# AUDIO.net
KiCad netlist of a schematic drawn in Altium Designer
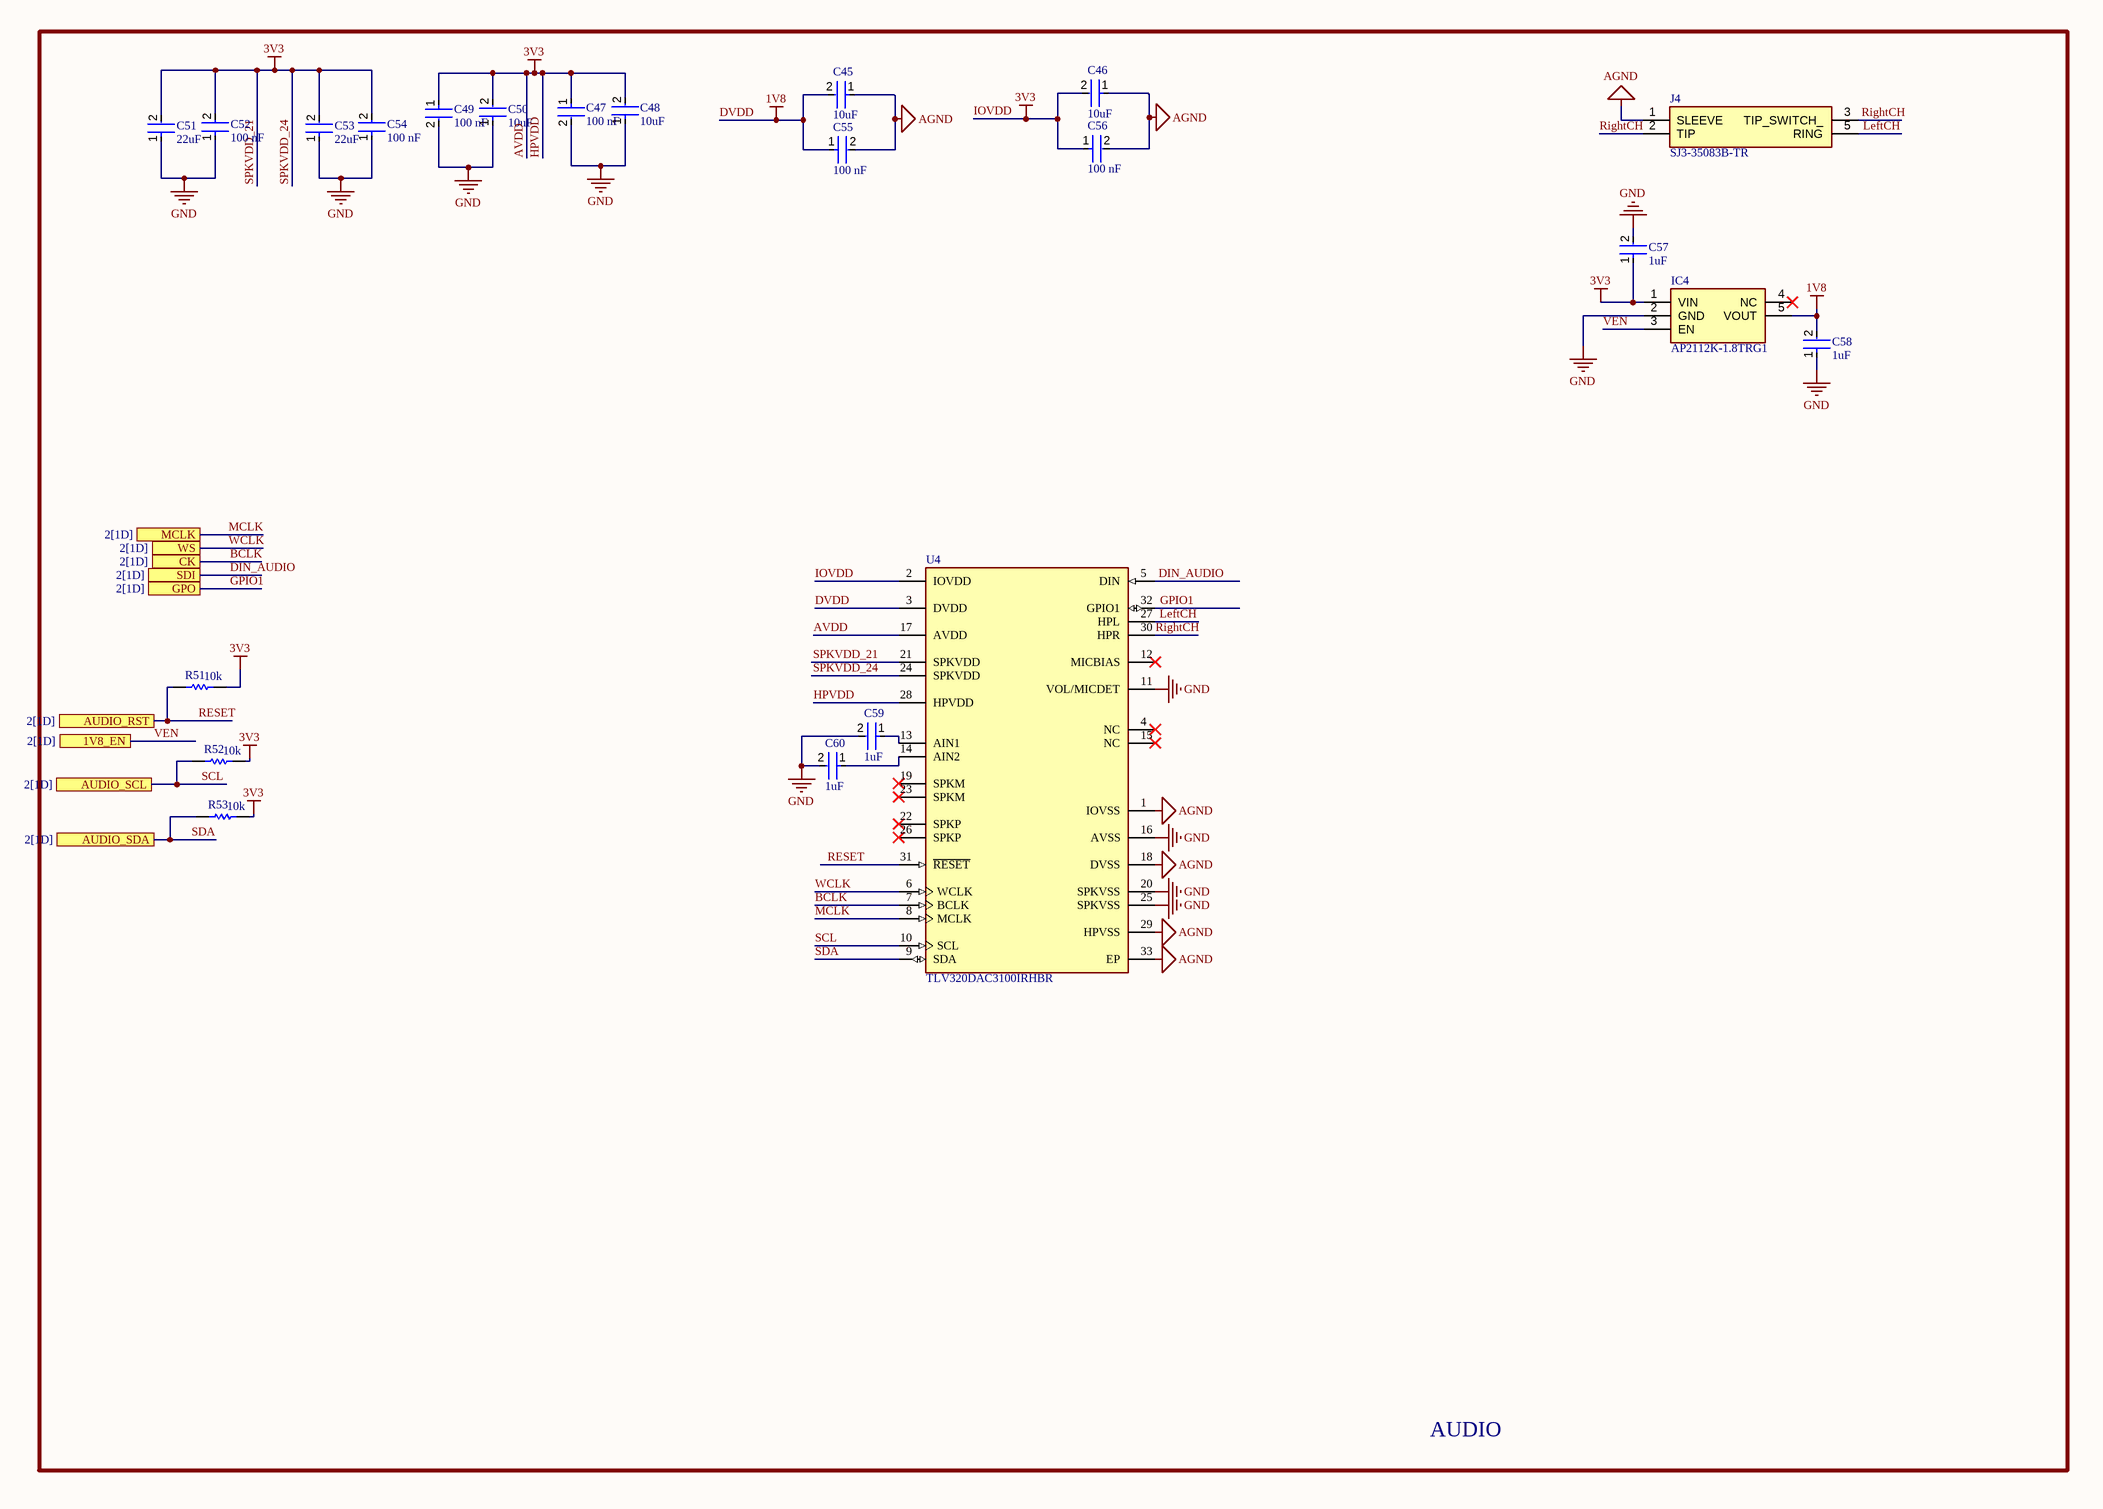
[diagram p0: AUDIO.SchDoc]

(export (version "E")
  (design (tool "Eeschema 10.0.6"))
  (components
    (comp (ref "C45")
      (value "GRM21BR61E106MA73L")
      (footprint "FP-GRM21B-0_15-IPC_A")
      (description "Chip Multilayer Ceramic Capacitors for General Purpose, 0805, 10uF, X5R, 15%, 20%, 25V")
      (fields (field (name "TOLERANCE") "20%") (field (name "CAPACITANCE") "10uF"))
      (libsource (lib "Altium Content Vault") (part "b4654b650e69147ec39a6b967a45e02"))
    )
    (comp (ref "C46")
      (value "GRM21BR61E106MA73L")
      (footprint "FP-GRM21B-0_15-IPC_A")
      (description "Chip Multilayer Ceramic Capacitors for General Purpose, 0805, 10uF, X5R, 15%, 20%, 25V")
      (fields (field (name "TOLERANCE") "20%") (field (name "CAPACITANCE") "10uF"))
      (libsource (lib "Altium Content Vault") (part "b4654b650e69147ec39a6b967a45e02"))
    )
    (comp (ref "C47")
      (value "100 nF")
      (footprint "FP-CC0603-DA-MFG")
      (description "CAP CER 0.1UF 16V X7R 0603")
      (fields
        (field (name "OCTOPART") "https://octopart.com/cc0603krx7r7bb104-yageo-192941")
        (field (name "TOLERANCE") "0.1")
      )
      (libsource (lib "Altium Content Vault") (part "11868f565c42a9108669ba33697ecf6"))
    )
    (comp (ref "C48")
      (value "GRM21BR61E106MA73L")
      (footprint "FP-GRM21B-0_15-IPC_A")
      (description "Chip Multilayer Ceramic Capacitors for General Purpose, 0805, 10uF, X5R, 15%, 20%, 25V")
      (fields (field (name "TOLERANCE") "20%") (field (name "CAPACITANCE") "10uF"))
      (libsource (lib "Altium Content Vault") (part "b4654b650e69147ec39a6b967a45e02"))
    )
    (comp (ref "C49")
      (value "100 nF")
      (footprint "FP-CC0603-DA-MFG")
      (description "CAP CER 0.1UF 16V X7R 0603")
      (fields
        (field (name "OCTOPART") "https://octopart.com/cc0603krx7r7bb104-yageo-192941")
        (field (name "TOLERANCE") "0.1")
      )
      (libsource (lib "Altium Content Vault") (part "11868f565c42a9108669ba33697ecf6"))
    )
    (comp (ref "C50")
      (value "GRM21BR61E106MA73L")
      (footprint "FP-GRM21B-0_15-IPC_A")
      (description "Chip Multilayer Ceramic Capacitors for General Purpose, 0805, 10uF, X5R, 15%, 20%, 25V")
      (fields (field (name "TOLERANCE") "20%") (field (name "CAPACITANCE") "10uF"))
      (libsource (lib "Altium Content Vault") (part "b4654b650e69147ec39a6b967a45e02"))
    )
    (comp (ref "C51")
      (value "EMK325B7226MM-PR")
      (footprint "FP-1210-L_3_2_0_3-W_2_5_0-IPC_A")
      (description "None")
      (fields (field (name "CAPACITANCE") "22uF") (field (name "TOLERANCE") "20%"))
      (libsource (lib "Altium Content Vault") (part "02cd4be3c70576c341d710602a673aa"))
    )
    (comp (ref "C52")
      (value "100 nF")
      (footprint "FP-CC0603-DA-MFG")
      (description "CAP CER 0.1UF 16V X7R 0603")
      (fields
        (field (name "OCTOPART") "https://octopart.com/cc0603krx7r7bb104-yageo-192941")
        (field (name "TOLERANCE") "0.1")
      )
      (libsource (lib "Altium Content Vault") (part "11868f565c42a9108669ba33697ecf6"))
    )
    (comp (ref "C53")
      (value "EMK325B7226MM-PR")
      (footprint "FP-1210-L_3_2_0_3-W_2_5_0-IPC_A")
      (description "None")
      (fields (field (name "CAPACITANCE") "22uF") (field (name "TOLERANCE") "20%"))
      (libsource (lib "Altium Content Vault") (part "02cd4be3c70576c341d710602a673aa"))
    )
    (comp (ref "C54")
      (value "100 nF")
      (footprint "FP-CC0603-DA-MFG")
      (description "CAP CER 0.1UF 16V X7R 0603")
      (fields
        (field (name "OCTOPART") "https://octopart.com/cc0603krx7r7bb104-yageo-192941")
        (field (name "TOLERANCE") "0.1")
      )
      (libsource (lib "Altium Content Vault") (part "11868f565c42a9108669ba33697ecf6"))
    )
    (comp (ref "C55")
      (value "100 nF")
      (footprint "FP-CC0603-DA-MFG")
      (description "CAP CER 0.1UF 16V X7R 0603")
      (fields
        (field (name "OCTOPART") "https://octopart.com/cc0603krx7r7bb104-yageo-192941")
        (field (name "TOLERANCE") "0.1")
      )
      (libsource (lib "Altium Content Vault") (part "11868f565c42a9108669ba33697ecf6"))
    )
    (comp (ref "C56")
      (value "100 nF")
      (footprint "FP-CC0603-DA-MFG")
      (description "CAP CER 0.1UF 16V X7R 0603")
      (fields
        (field (name "OCTOPART") "https://octopart.com/cc0603krx7r7bb104-yageo-192941")
        (field (name "TOLERANCE") "0.1")
      )
      (libsource (lib "Altium Content Vault") (part "11868f565c42a9108669ba33697ecf6"))
    )
    (comp (ref "C57")
      (value "CL21F105ZAFNNNF")
      (footprint "FP-CL21-IPC_B")
      (description "CL21 Series 0805 1uF 25V -20/+80% Tolerance Y5V Multilayer Ceramic Chip Capacitor")
      (fields (field (name "CAPACITANCE") "1uF") (field (name "TOLERANCE") "80%"))
      (libsource (lib "Altium Content Vault") (part "b4654b650e69147ec39a6b967a45e02"))
    )
    (comp (ref "C58")
      (value "CL21F105ZAFNNNF")
      (footprint "FP-CL21-IPC_B")
      (description "CL21 Series 0805 1uF 25V -20/+80% Tolerance Y5V Multilayer Ceramic Chip Capacitor")
      (fields (field (name "CAPACITANCE") "1uF") (field (name "TOLERANCE") "80%"))
      (libsource (lib "Altium Content Vault") (part "b4654b650e69147ec39a6b967a45e02"))
    )
    (comp (ref "C59")
      (value "CL21F105ZAFNNNF")
      (footprint "FP-CL21-IPC_B")
      (description "CL21 Series 0805 1uF 25V -20/+80% Tolerance Y5V Multilayer Ceramic Chip Capacitor")
      (fields (field (name "CAPACITANCE") "1uF") (field (name "TOLERANCE") "80%"))
      (libsource (lib "Altium Content Vault") (part "b4654b650e69147ec39a6b967a45e02"))
    )
    (comp (ref "C60")
      (value "CL21F105ZAFNNNF")
      (footprint "FP-CL21-IPC_B")
      (description "CL21 Series 0805 1uF 25V -20/+80% Tolerance Y5V Multilayer Ceramic Chip Capacitor")
      (fields (field (name "CAPACITANCE") "1uF") (field (name "TOLERANCE") "80%"))
      (libsource (lib "Altium Content Vault") (part "b4654b650e69147ec39a6b967a45e02"))
    )
    (comp (ref "IC4")
      (value "AP2112K-1.8TRG1")
      (footprint "SamacSys:SOT95P285X140-5N")
      (description "Integrated Circuit")
      (fields (field (name "MOUSER PART NUMBER") "621-AP2112K-1.8TRG1"))
      (libsource (lib "*") (part "AP2112K-1.8TRG1"))
    )
    (comp (ref "J4")
      (value "SJ3-35083B-TR")
      (footprint "SamacSys:SJ335083BTR")
      (description "Connector")
      (fields (field (name "MOUSER PART NUMBER") "179-SJ3-35083B-TR"))
      (libsource (lib "*") (part "SJ3-35083B-TR"))
    )
    (comp (ref "R51")
      (value "10k")
      (footprint "RESC1609X55X30NL10T20")
      (fields (field (name "MANUFACTURER") "Vishay Dale") (field (name "PART NUMBER") "TNPW060310K0BEEN"))
      (libsource (lib "Altium Content Vault") (part "RES"))
    )
    (comp (ref "R52")
      (value "10k")
      (footprint "RESC1609X55X30NL10T20")
      (fields (field (name "MANUFACTURER") "Vishay Dale") (field (name "PART NUMBER") "TNPW060310K0BEEN"))
      (libsource (lib "Altium Content Vault") (part "RES"))
    )
    (comp (ref "R53")
      (value "10k")
      (footprint "RESC1609X55X30NL10T20")
      (fields (field (name "MANUFACTURER") "Vishay Dale") (field (name "PART NUMBER") "TNPW060310K0BEEN"))
      (libsource (lib "Altium Content Vault") (part "RES"))
    )
    (comp (ref "U4")
      (value "TLV320DAC3100IRHBR")
      (footprint "FP-RHB0032E-IPC_C")
      (description "IC DAC 24BIT 192K 32VQFN")
      (libsource (lib "Altium Content Vault") (part "975daa9c6031e18a2fb7c6c6de752c7"))
    )
  )
  (nets
    (net (code "2") (name "/BCLK") (class "Default")
      (node (ref "U4") (pin "7") (pinfunction "BCLK_7") (pintype "input"))
    )
    (net (code "3") (name "/DIN_AUDIO") (class "Default")
      (node (ref "U4") (pin "5") (pinfunction "DIN_5") (pintype "input"))
    )
    (net (code "4") (name "/GPIO1") (class "Default")
      (node (ref "U4") (pin "32") (pinfunction "GPIO1_32") (pintype "bidirectional"))
    )
    (net (code "5") (name "/LeftCH") (class "Default")
      (node (ref "J4") (pin "5") (pinfunction "RING_5") (pintype "passive"))
      (node (ref "U4") (pin "27") (pinfunction "HPL_27") (pintype "passive"))
    )
    (net (code "6") (name "/MCLK") (class "Default")
      (node (ref "U4") (pin "8") (pinfunction "MCLK_8") (pintype "input"))
    )
    (net (code "7") (name "/RESET") (class "Default")
      (node (ref "R51") (pin "2") (pinfunction "2_2") (pintype "passive"))
      (node (ref "U4") (pin "31") (pinfunction "~{RESET}_31") (pintype "input"))
    )
    (net (code "8") (name "/RightCH") (class "Default")
      (node (ref "J4") (pin "2") (pinfunction "TIP_2") (pintype "passive"))
      (node (ref "J4") (pin "3") (pinfunction "TIP_SWITCH__3") (pintype "passive"))
      (node (ref "U4") (pin "30") (pinfunction "HPR_30") (pintype "passive"))
    )
    (net (code "9") (name "/SCL") (class "Default")
      (node (ref "R52") (pin "2") (pinfunction "2_2") (pintype "passive"))
      (node (ref "U4") (pin "10") (pinfunction "SCL_10") (pintype "input"))
    )
    (net (code "10") (name "/SDA") (class "Default")
      (node (ref "R53") (pin "2") (pinfunction "2_2") (pintype "passive"))
      (node (ref "U4") (pin "9") (pinfunction "SDA_9") (pintype "bidirectional"))
    )
    (net (code "11") (name "/VEN") (class "Default")
      (node (ref "IC4") (pin "3") (pinfunction "EN_3") (pintype "passive"))
    )
    (net (code "12") (name "/WCLK") (class "Default")
      (node (ref "U4") (pin "6") (pinfunction "WCLK_6") (pintype "input"))
    )
    (net (code "13") (name "1V8") (class "Default")
      (node (ref "C45") (pin "2") (pinfunction "2_2") (pintype "passive"))
      (node (ref "C55") (pin "1") (pinfunction "1_1") (pintype "passive"))
      (node (ref "C58") (pin "2") (pinfunction "2_2") (pintype "passive"))
      (node (ref "IC4") (pin "5") (pinfunction "VOUT_5") (pintype "passive"))
      (node (ref "U4") (pin "3") (pinfunction "DVDD_3") (pintype "power_in"))
    )
    (net (code "14") (name "3V3") (class "Default")
      (node (ref "C46") (pin "2") (pinfunction "2_2") (pintype "passive"))
      (node (ref "C47") (pin "1") (pinfunction "1_1") (pintype "passive"))
      (node (ref "C48") (pin "2") (pinfunction "2_2") (pintype "passive"))
      (node (ref "C49") (pin "1") (pinfunction "1_1") (pintype "passive"))
      (node (ref "C50") (pin "2") (pinfunction "2_2") (pintype "passive"))
      (node (ref "C51") (pin "2") (pinfunction "2_2") (pintype "passive"))
      (node (ref "C52") (pin "2") (pinfunction "2_2") (pintype "passive"))
      (node (ref "C53") (pin "2") (pinfunction "2_2") (pintype "passive"))
      (node (ref "C54") (pin "2") (pinfunction "2_2") (pintype "passive"))
      (node (ref "C56") (pin "1") (pinfunction "1_1") (pintype "passive"))
      (node (ref "C57") (pin "1") (pinfunction "1_1") (pintype "passive"))
      (node (ref "IC4") (pin "1") (pinfunction "VIN_1") (pintype "passive"))
      (node (ref "R51") (pin "1") (pinfunction "1_1") (pintype "passive"))
      (node (ref "R52") (pin "1") (pinfunction "1_1") (pintype "passive"))
      (node (ref "R53") (pin "1") (pinfunction "1_1") (pintype "passive"))
      (node (ref "U4") (pin "17") (pinfunction "AVDD_17") (pintype "power_in"))
      (node (ref "U4") (pin "2") (pinfunction "IOVDD_2") (pintype "power_in"))
      (node (ref "U4") (pin "21") (pinfunction "SPKVDD_21") (pintype "power_in"))
      (node (ref "U4") (pin "24") (pinfunction "SPKVDD_24") (pintype "power_in"))
      (node (ref "U4") (pin "28") (pinfunction "HPVDD_28") (pintype "power_in"))
    )
    (net (code "15") (name "AGND") (class "Default")
      (node (ref "C45") (pin "1") (pinfunction "1_1") (pintype "passive"))
      (node (ref "C46") (pin "1") (pinfunction "1_1") (pintype "passive"))
      (node (ref "C55") (pin "2") (pinfunction "2_2") (pintype "passive"))
      (node (ref "C56") (pin "2") (pinfunction "2_2") (pintype "passive"))
      (node (ref "J4") (pin "1") (pinfunction "SLEEVE_1") (pintype "passive"))
      (node (ref "U4") (pin "1") (pinfunction "IOVSS_1") (pintype "power_in"))
      (node (ref "U4") (pin "18") (pinfunction "DVSS_18") (pintype "power_in"))
      (node (ref "U4") (pin "29") (pinfunction "HPVSS_29") (pintype "power_in"))
      (node (ref "U4") (pin "33") (pinfunction "EP_33") (pintype "power_in"))
    )
    (net (code "16") (name "GND") (class "Default")
      (node (ref "C47") (pin "2") (pinfunction "2_2") (pintype "passive"))
      (node (ref "C48") (pin "1") (pinfunction "1_1") (pintype "passive"))
      (node (ref "C49") (pin "2") (pinfunction "2_2") (pintype "passive"))
      (node (ref "C50") (pin "1") (pinfunction "1_1") (pintype "passive"))
      (node (ref "C51") (pin "1") (pinfunction "1_1") (pintype "passive"))
      (node (ref "C52") (pin "1") (pinfunction "1_1") (pintype "passive"))
      (node (ref "C53") (pin "1") (pinfunction "1_1") (pintype "passive"))
      (node (ref "C54") (pin "1") (pinfunction "1_1") (pintype "passive"))
      (node (ref "C57") (pin "2") (pinfunction "2_2") (pintype "passive"))
      (node (ref "C58") (pin "1") (pinfunction "1_1") (pintype "passive"))
      (node (ref "C59") (pin "2") (pinfunction "2_2") (pintype "passive"))
      (node (ref "C60") (pin "2") (pinfunction "2_2") (pintype "passive"))
      (node (ref "IC4") (pin "2") (pinfunction "GND_2") (pintype "passive"))
      (node (ref "U4") (pin "11") (pinfunction "VOL/MICDET_11") (pintype "passive"))
      (node (ref "U4") (pin "16") (pinfunction "AVSS_16") (pintype "power_in"))
      (node (ref "U4") (pin "20") (pinfunction "SPKVSS_20") (pintype "power_in"))
      (node (ref "U4") (pin "25") (pinfunction "SPKVSS_25") (pintype "power_in"))
    )
    (net (code "17") (name "Net-(U4-AIN1)") (class "Default")
      (node (ref "C59") (pin "1") (pinfunction "1_1") (pintype "passive"))
      (node (ref "U4") (pin "13") (pinfunction "AIN1_13") (pintype "passive"))
    )
    (net (code "18") (name "Net-(U4-AIN2)") (class "Default")
      (node (ref "C60") (pin "1") (pinfunction "1_1") (pintype "passive"))
      (node (ref "U4") (pin "14") (pinfunction "AIN2_14") (pintype "passive"))
    )
    (net (code "19") (name "unconnected-(IC4-NC-Pad4)") (class "Default")
      (node (ref "IC4") (pin "4") (pinfunction "NC_4") (pintype "passive+no_connect"))
    )
    (net (code "20") (name "unconnected-(U4-MICBIAS-Pad12)") (class "Default")
      (node (ref "U4") (pin "12") (pinfunction "MICBIAS_12") (pintype "passive+no_connect"))
    )
    (net (code "21") (name "unconnected-(U4-NC-Pad4)") (class "Default")
      (node (ref "U4") (pin "4") (pinfunction "NC_4") (pintype "passive+no_connect"))
    )
    (net (code "22") (name "unconnected-(U4-NC-Pad15)") (class "Default")
      (node (ref "U4") (pin "15") (pinfunction "NC_15") (pintype "passive+no_connect"))
    )
    (net (code "23") (name "unconnected-(U4-SPKM-Pad19)") (class "Default")
      (node (ref "U4") (pin "19") (pinfunction "SPKM_19") (pintype "passive+no_connect"))
    )
    (net (code "24") (name "unconnected-(U4-SPKM-Pad23)") (class "Default")
      (node (ref "U4") (pin "23") (pinfunction "SPKM_23") (pintype "passive+no_connect"))
    )
    (net (code "25") (name "unconnected-(U4-SPKP-Pad22)") (class "Default")
      (node (ref "U4") (pin "22") (pinfunction "SPKP_22") (pintype "passive+no_connect"))
    )
    (net (code "26") (name "unconnected-(U4-SPKP-Pad26)") (class "Default")
      (node (ref "U4") (pin "26") (pinfunction "SPKP_26") (pintype "passive+no_connect"))
    )
  )
)
